# Master_MicroController_Core.net
KiCad netlist of a schematic drawn in Altium Designer
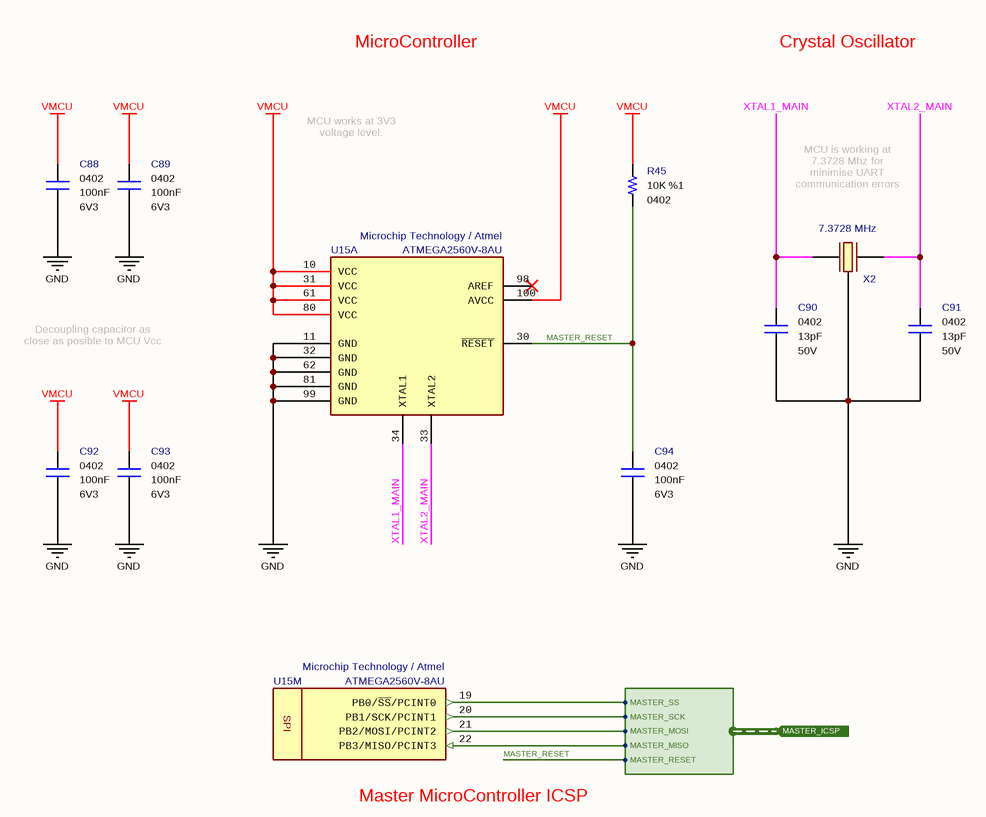
[diagram p0: Master MicroController Core.SchDoc]

(export (version "E")
  (design (tool "Eeschema 10.0.6"))
  (components
    (comp (ref "C88")
      (value "100nF")
      (footprint "CAPACITOR_0402")
      (description "Capacitor - 100nF [0402-6V3] (Ceramic)")
      (fields
        (field (name "TOLERANCE") "%10")
        (field (name "CASE") "0402")
        (field (name "VOLTAGE") "6V3")
        (field (name "MANUFACTURER PART NUMBER") "04026D104KAT4A")
      )
      (libsource (lib "Ovoo_Library") (part "Capacitor - 100nF [0402-6V3]"))
    )
    (comp (ref "C89")
      (value "100nF")
      (footprint "CAPACITOR_0402")
      (description "Capacitor - 100nF [0402-6V3] (Ceramic)")
      (fields
        (field (name "TOLERANCE") "%10")
        (field (name "CASE") "0402")
        (field (name "VOLTAGE") "6V3")
        (field (name "MANUFACTURER PART NUMBER") "04026D104KAT4A")
      )
      (libsource (lib "Ovoo_Library") (part "Capacitor - 100nF [0402-6V3]"))
    )
    (comp (ref "C90")
      (value "13pF")
      (footprint "CAPACITOR_0402")
      (description "Capacitor - 13pF [0402] (Ceramic)")
      (fields
        (field (name "TOLERANCE") "1%")
        (field (name "VOLTAGE") "50V")
        (field (name "CASE") "0402")
        (field (name "MANUFACTURER PART NUMBER") "CBR04C130F5GAC")
      )
      (libsource (lib "Ovoo_Library") (part "Capacitor - 13pF [0402-50V]"))
    )
    (comp (ref "C91")
      (value "13pF")
      (footprint "CAPACITOR_0402")
      (description "Capacitor - 13pF [0402] (Ceramic)")
      (fields
        (field (name "TOLERANCE") "1%")
        (field (name "VOLTAGE") "50V")
        (field (name "CASE") "0402")
        (field (name "MANUFACTURER PART NUMBER") "CBR04C130F5GAC")
      )
      (libsource (lib "Ovoo_Library") (part "Capacitor - 13pF [0402-50V]"))
    )
    (comp (ref "C92")
      (value "100nF")
      (footprint "CAPACITOR_0402")
      (description "Capacitor - 100nF [0402-6V3] (Ceramic)")
      (fields
        (field (name "TOLERANCE") "%10")
        (field (name "CASE") "0402")
        (field (name "VOLTAGE") "6V3")
        (field (name "MANUFACTURER PART NUMBER") "04026D104KAT4A")
      )
      (libsource (lib "Ovoo_Library") (part "Capacitor - 100nF [0402-6V3]"))
    )
    (comp (ref "C93")
      (value "100nF")
      (footprint "CAPACITOR_0402")
      (description "Capacitor - 100nF [0402-6V3] (Ceramic)")
      (fields
        (field (name "TOLERANCE") "%10")
        (field (name "CASE") "0402")
        (field (name "VOLTAGE") "6V3")
        (field (name "MANUFACTURER PART NUMBER") "04026D104KAT4A")
      )
      (libsource (lib "Ovoo_Library") (part "Capacitor - 100nF [0402-6V3]"))
    )
    (comp (ref "C94")
      (value "100nF")
      (footprint "CAPACITOR_0402")
      (description "Capacitor - 100nF [0402-6V3] (Ceramic)")
      (fields
        (field (name "TOLERANCE") "%10")
        (field (name "CASE") "0402")
        (field (name "VOLTAGE") "6V3")
        (field (name "MANUFACTURER PART NUMBER") "04026D104KAT4A")
      )
      (libsource (lib "Ovoo_Library") (part "Capacitor - 100nF [0402-6V3]"))
    )
    (comp (ref "R45")
      (value "10K")
      (footprint "RESISTOR_0402")
      (description "Thick Film Resistors - SMD 1/16 W 10 Kohms 1%")
      (fields
        (field (name "TOLERANCE") "%1")
        (field (name "CASE") "0402")
        (field (name "MANUFACTURER PART NUMBER") "CRCW040210K0FKED")
        (field (name "MOUSER PART NUMBER") "71-CRCW0402-10K-E3")
      )
      (libsource (lib "Ovoo_Library") (part "Resistor - 10K"))
    )
    (comp (ref "U15")
      (value "8-bit MicroController")
      (footprint "TQFP100")
      (description "8-bit Microcontrollers - MCU 256kB Flash 4kB EEPROM 86 I/O Pins")
      (fields
        (field (name "MOUSER_PART_NUMBER") "556-ATMEGA2560V8AU")
        (field (name "MANUFACTURER_PART_NUMBER") "ATMEGA2560V-8AU")
        (field (name "MANUFACTURER_NAME") "Microchip Technology / Atmel")
        (field (name "MOUSER PART NUMBER") "556-ATMEGA2560V8AU")
        (field (name "MANUFACTURER PART NUMBER") "ATMEGA2560V-8AU")
        (field (name "MANUFACTURER NAME") "Microchip Technology / Atmel")
      )
      (libsource (lib "Ovoo_Library") (part "IC - ATMEGA2560V-8AU"))
    )
    (comp (ref "X2")
      (value "7.3728 MHz")
      (footprint "ABRACON_CRYSTAL")
      (description "Crystals 7.3728MHz 18pF -40C +85C")
      (fields
        (field (name "MANUFACTURER PART NUMBER") "ABMM2-7.3728MHZ-E2-T")
        (field (name "MOUSER PART NUMBER") "815-ABMM2-7.3-E2-T")
      )
      (libsource (lib "Ovoo_Library") (part "Crystal - 7.3728 MHz (Abracon)"))
    )
  )
  (nets
    (net (code "2") (name "/MASTER_MISO") (class "Default")
      (node (ref "U15") (pin "22") (pinfunction "PB3/MISO/PCINT3_22") (pintype "passive"))
    )
    (net (code "3") (name "/MASTER_MOSI") (class "Default")
      (node (ref "U15") (pin "21") (pinfunction "PB2/MOSI/PCINT2_21") (pintype "passive"))
    )
    (net (code "4") (name "/MASTER_RESET") (class "Default")
      (node (ref "C94") (pin "2") (pinfunction "2_2") (pintype "passive"))
      (node (ref "R45") (pin "1") (pinfunction "1_1") (pintype "passive"))
      (node (ref "U15") (pin "30") (pinfunction "~{RESET}_30") (pintype "passive"))
    )
    (net (code "5") (name "/MASTER_SCK") (class "Default")
      (node (ref "U15") (pin "20") (pinfunction "PB1/SCK/PCINT1_20") (pintype "passive"))
    )
    (net (code "6") (name "/MASTER_SS") (class "Default")
      (node (ref "U15") (pin "19") (pinfunction "PB0/~{SS}/PCINT0_19") (pintype "passive"))
    )
    (net (code "7") (name "/XTAL1_MAIN") (class "Default")
      (node (ref "C90") (pin "2") (pinfunction "2_2") (pintype "passive"))
      (node (ref "U15") (pin "34") (pinfunction "XTAL1_34") (pintype "passive"))
      (node (ref "X2") (pin "3") (pinfunction "OUT/IN_3") (pintype "passive"))
    )
    (net (code "8") (name "/XTAL2_MAIN") (class "Default")
      (node (ref "C91") (pin "2") (pinfunction "2_2") (pintype "passive"))
      (node (ref "U15") (pin "33") (pinfunction "XTAL2_33") (pintype "passive"))
      (node (ref "X2") (pin "1") (pinfunction "IN/OUT_1") (pintype "passive"))
    )
    (net (code "10") (name "GND") (class "Default")
      (node (ref "C88") (pin "1") (pinfunction "1_1") (pintype "passive"))
      (node (ref "C89") (pin "1") (pinfunction "1_1") (pintype "passive"))
      (node (ref "C90") (pin "1") (pinfunction "1_1") (pintype "passive"))
      (node (ref "C91") (pin "1") (pinfunction "1_1") (pintype "passive"))
      (node (ref "C92") (pin "1") (pinfunction "1_1") (pintype "passive"))
      (node (ref "C93") (pin "1") (pinfunction "1_1") (pintype "passive"))
      (node (ref "C94") (pin "1") (pinfunction "1_1") (pintype "passive"))
      (node (ref "U15") (pin "11") (pinfunction "GND_11") (pintype "passive"))
      (node (ref "U15") (pin "32") (pinfunction "GND_32") (pintype "passive"))
      (node (ref "U15") (pin "62") (pinfunction "GND_62") (pintype "passive"))
      (node (ref "U15") (pin "81") (pinfunction "GND_81") (pintype "passive"))
      (node (ref "U15") (pin "99") (pinfunction "GND_99") (pintype "passive"))
      (node (ref "X2") (pin "2") (pinfunction "GND_2") (pintype "passive"))
    )
    (net (code "11") (name "VMCU") (class "Default")
      (node (ref "C88") (pin "2") (pinfunction "2_2") (pintype "passive"))
      (node (ref "C89") (pin "2") (pinfunction "2_2") (pintype "passive"))
      (node (ref "C92") (pin "2") (pinfunction "2_2") (pintype "passive"))
      (node (ref "C93") (pin "2") (pinfunction "2_2") (pintype "passive"))
      (node (ref "R45") (pin "2") (pinfunction "2_2") (pintype "passive"))
      (node (ref "U15") (pin "10") (pinfunction "VCC_10") (pintype "power_in"))
      (node (ref "U15") (pin "100") (pinfunction "AVCC_100") (pintype "passive"))
      (node (ref "U15") (pin "31") (pinfunction "VCC_31") (pintype "power_in"))
      (node (ref "U15") (pin "61") (pinfunction "VCC_61") (pintype "power_in"))
      (node (ref "U15") (pin "80") (pinfunction "VCC_80") (pintype "power_in"))
    )
    (net (code "12") (name "unconnected-(U15A-AREF-Pad98)") (class "Default")
      (node (ref "U15") (pin "98") (pinfunction "AREF_98") (pintype "passive+no_connect"))
    )
    (net (code "13") (name "unconnected-(X2-GND-Pad4)") (class "Default")
      (node (ref "X2") (pin "4") (pinfunction "GND_4") (pintype "passive"))
    )
  )
)
